# detonador.net
KiCad netlist of a schematic drawn in EAGLE
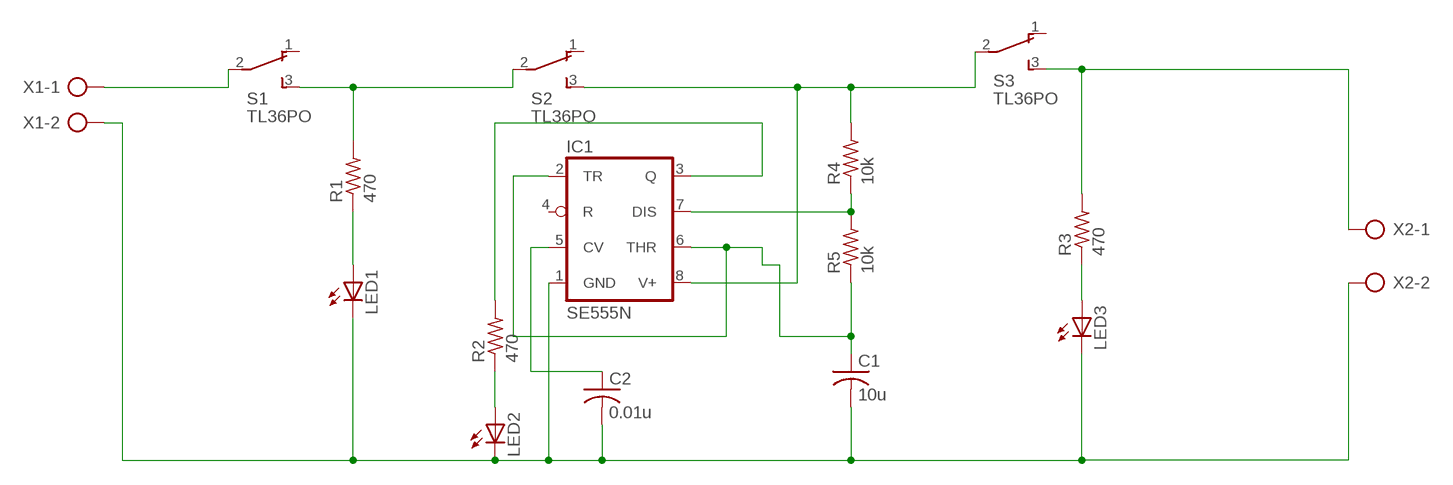
[diagram p0: schematic, sheet 1]

(export (version "E")
  (design (tool "Eeschema 10.0.6"))
  (components
    (comp (ref "C1")
      (value "10u")
      (footprint "eagle-import:C025-040X050")
      (libsource (lib "eagle-import") (part "C-US025-040X050"))
    )
    (comp (ref "C2")
      (value "0.01u")
      (footprint "eagle-import:C025-040X050")
      (libsource (lib "eagle-import") (part "C-US025-040X050"))
    )
    (comp (ref "IC1")
      (value "SE555N")
      (footprint "eagle-import:DIL08-ROUND")
      (libsource (lib "eagle-import") (part "555NSE"))
    )
    (comp (ref "LED1")
      (value "LED5MM")
      (footprint "eagle-import:LED5MM")
      (libsource (lib "eagle-import") (part "LED5MM"))
    )
    (comp (ref "LED2")
      (value "LED5MM")
      (footprint "eagle-import:LED5MM")
      (libsource (lib "eagle-import") (part "LED5MM"))
    )
    (comp (ref "LED3")
      (value "LED5MM")
      (footprint "eagle-import:LED5MM")
      (libsource (lib "eagle-import") (part "LED5MM"))
    )
    (comp (ref "R1")
      (value "470")
      (footprint "eagle-import:0207_12")
      (libsource (lib "eagle-import") (part "R-US_0207/12"))
    )
    (comp (ref "R2")
      (value "470")
      (footprint "eagle-import:0207_12")
      (libsource (lib "eagle-import") (part "R-US_0207/12"))
    )
    (comp (ref "R3")
      (value "470")
      (footprint "eagle-import:0207_12")
      (libsource (lib "eagle-import") (part "R-US_0207/12"))
    )
    (comp (ref "R4")
      (value "10k")
      (footprint "eagle-import:0207_10")
      (libsource (lib "eagle-import") (part "R-US_0207/10"))
    )
    (comp (ref "R5")
      (value "10k")
      (footprint "eagle-import:0207_10")
      (libsource (lib "eagle-import") (part "R-US_0207/10"))
    )
    (comp (ref "S1")
      (value "TL36PO")
      (footprint "eagle-import:TL3XPO")
      (libsource (lib "eagle-import") (part "TL36PO"))
    )
    (comp (ref "S2")
      (value "TL36PO")
      (footprint "eagle-import:TL3XPO")
      (libsource (lib "eagle-import") (part "TL36PO"))
    )
    (comp (ref "S3")
      (value "TL36PO")
      (footprint "eagle-import:TL3XPO")
      (libsource (lib "eagle-import") (part "TL36PO"))
    )
    (comp (ref "X1")
      (value "AK500/2-H")
      (footprint "eagle-import:AK500_2-H")
      (libsource (lib "eagle-import") (part "AK500/2-H"))
    )
    (comp (ref "X2")
      (value "AK500/2-H")
      (footprint "eagle-import:AK500_2-H")
      (libsource (lib "eagle-import") (part "AK500/2-H"))
    )
  )
  (nets
    (net (code "1") (name "Net-(IC1-CV)") (class "Default")
      (node (ref "C2") (pin "1") (pinfunction "1_1") (pintype "passive"))
      (node (ref "IC1") (pin "5") (pinfunction "CV_5") (pintype "input"))
    )
    (net (code "2") (name "Net-(IC1-DIS)") (class "Default")
      (node (ref "IC1") (pin "7") (pinfunction "DIS_7") (pintype "input"))
      (node (ref "R4") (pin "1") (pinfunction "1_1") (pintype "passive"))
      (node (ref "R5") (pin "2") (pinfunction "2_2") (pintype "passive"))
    )
    (net (code "3") (name "Net-(IC1-GND)") (class "Default")
      (node (ref "C1") (pin "2") (pinfunction "2_2") (pintype "passive"))
      (node (ref "C2") (pin "2") (pinfunction "2_2") (pintype "passive"))
      (node (ref "IC1") (pin "1") (pinfunction "GND_1") (pintype "power_in"))
      (node (ref "LED1") (pin "K") (pinfunction "C_K") (pintype "passive"))
      (node (ref "LED2") (pin "K") (pinfunction "C_K") (pintype "passive"))
      (node (ref "LED3") (pin "K") (pinfunction "C_K") (pintype "passive"))
      (node (ref "X1") (pin "2") (pinfunction "KL_2") (pintype "passive"))
      (node (ref "X2") (pin "2") (pinfunction "KL_2") (pintype "passive"))
    )
    (net (code "4") (name "Net-(IC1-Q)") (class "Default")
      (node (ref "IC1") (pin "3") (pinfunction "Q_3") (pintype "output"))
      (node (ref "R2") (pin "2") (pinfunction "2_2") (pintype "passive"))
    )
    (net (code "5") (name "Net-(IC1-THR)") (class "Default")
      (node (ref "C1") (pin "1") (pinfunction "1_1") (pintype "passive"))
      (node (ref "IC1") (pin "2") (pinfunction "TR_2") (pintype "input"))
      (node (ref "IC1") (pin "6") (pinfunction "THR_6") (pintype "input"))
      (node (ref "R5") (pin "1") (pinfunction "1_1") (pintype "passive"))
    )
    (net (code "6") (name "Net-(IC1-V+)") (class "Default")
      (node (ref "IC1") (pin "8") (pinfunction "V+_8") (pintype "power_in"))
      (node (ref "R4") (pin "2") (pinfunction "2_2") (pintype "passive"))
      (node (ref "S2") (pin "3") (pinfunction "S_3") (pintype "passive"))
      (node (ref "S3") (pin "2") (pinfunction "P_2") (pintype "passive"))
    )
    (net (code "7") (name "Net-(LED1-PadA)") (class "Default")
      (node (ref "LED1") (pin "A") (pinfunction "A_A") (pintype "passive"))
      (node (ref "R1") (pin "1") (pinfunction "1_1") (pintype "passive"))
    )
    (net (code "8") (name "Net-(LED2-PadA)") (class "Default")
      (node (ref "LED2") (pin "A") (pinfunction "A_A") (pintype "passive"))
      (node (ref "R2") (pin "1") (pinfunction "1_1") (pintype "passive"))
    )
    (net (code "9") (name "Net-(LED3-PadA)") (class "Default")
      (node (ref "LED3") (pin "A") (pinfunction "A_A") (pintype "passive"))
      (node (ref "R3") (pin "1") (pinfunction "1_1") (pintype "passive"))
    )
    (net (code "10") (name "Net-(S1-P)") (class "Default")
      (node (ref "S1") (pin "2") (pinfunction "P_2") (pintype "passive"))
      (node (ref "X1") (pin "1") (pinfunction "KL_1") (pintype "passive"))
    )
    (net (code "11") (name "Net-(S1-S)") (class "Default")
      (node (ref "R1") (pin "2") (pinfunction "2_2") (pintype "passive"))
      (node (ref "S1") (pin "3") (pinfunction "S_3") (pintype "passive"))
      (node (ref "S2") (pin "2") (pinfunction "P_2") (pintype "passive"))
    )
    (net (code "12") (name "Net-(S3-S)") (class "Default")
      (node (ref "R3") (pin "2") (pinfunction "2_2") (pintype "passive"))
      (node (ref "S3") (pin "3") (pinfunction "S_3") (pintype "passive"))
      (node (ref "X2") (pin "1") (pinfunction "KL_1") (pintype "passive"))
    )
    (net (code "13") (name "unconnected-(IC1-R-Pad4)") (class "Default")
      (node (ref "IC1") (pin "4") (pinfunction "R_4") (pintype "input"))
    )
    (net (code "14") (name "unconnected-(S1-O-Pad1)") (class "Default")
      (node (ref "S1") (pin "1") (pinfunction "O_1") (pintype "passive"))
    )
    (net (code "15") (name "unconnected-(S2-O-Pad1)") (class "Default")
      (node (ref "S2") (pin "1") (pinfunction "O_1") (pintype "passive"))
    )
    (net (code "16") (name "unconnected-(S3-O-Pad1)") (class "Default")
      (node (ref "S3") (pin "1") (pinfunction "O_1") (pintype "passive"))
    )
  )
)
